# electronics_2_2023.net
KiCad netlist of a schematic drawn in EAGLE
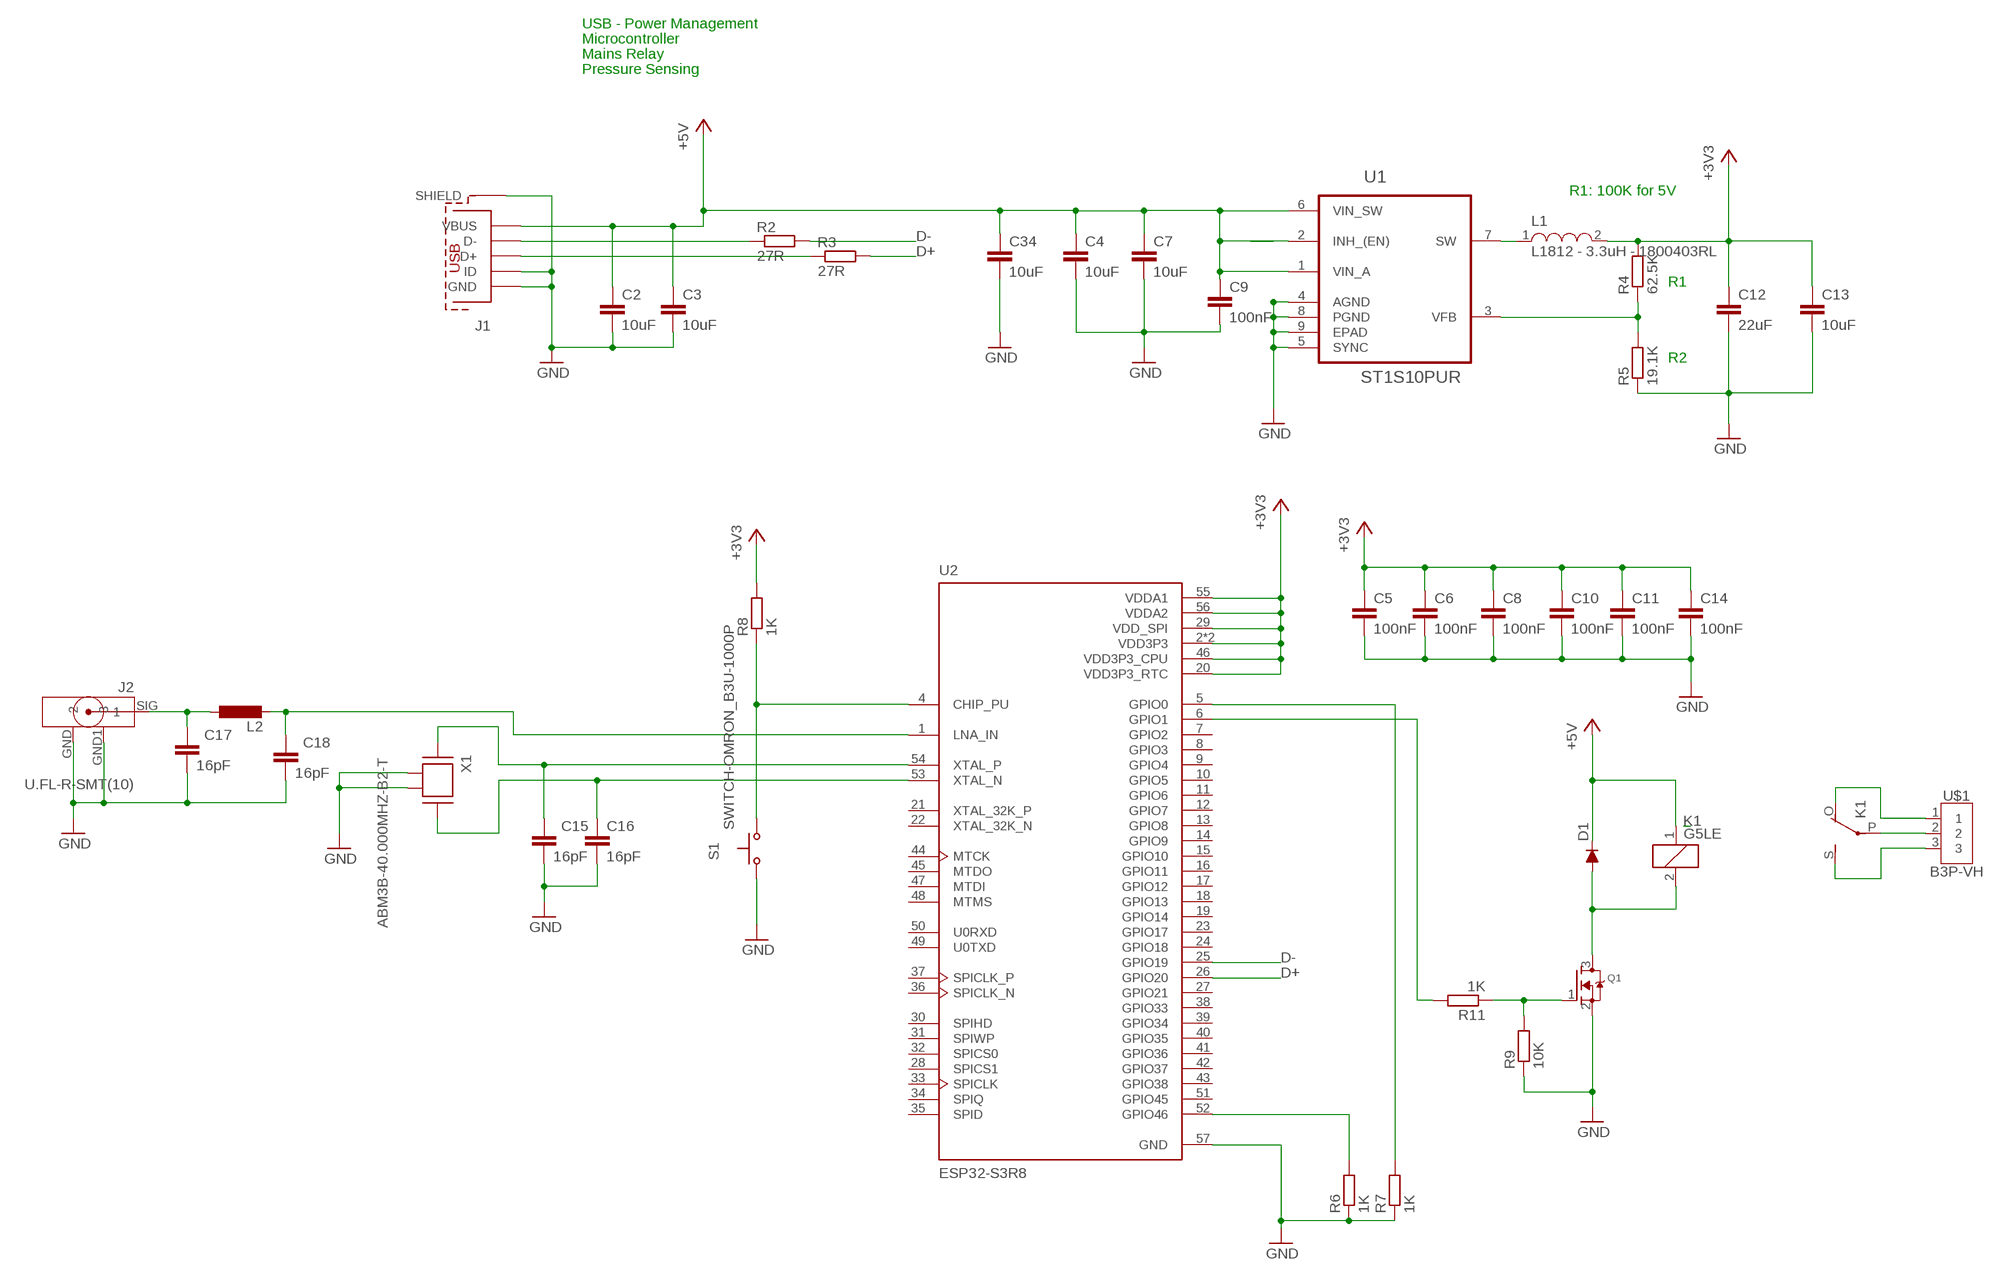
[diagram p0: schematic, sheet 1]
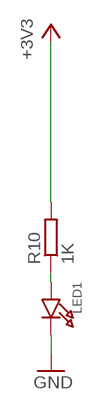
[diagram p1: schematic, sheet 2]

(export (version "E")
  (design (tool "Eeschema 10.0.6"))
  (components
    (comp (ref "C2")
      (value "10uF")
      (footprint "eagle-import:C0603")
      (libsource (lib "eagle-import") (part "C-EUC0603"))
    )
    (comp (ref "C3")
      (value "10uF")
      (footprint "eagle-import:C0603")
      (libsource (lib "eagle-import") (part "C-EUC0603"))
    )
    (comp (ref "C4")
      (value "10uF")
      (footprint "eagle-import:C0603")
      (libsource (lib "eagle-import") (part "resistor_C-EUC0603"))
    )
    (comp (ref "C5")
      (value "100nF")
      (footprint "eagle-import:C0402")
      (libsource (lib "eagle-import") (part "C-EUC0402"))
    )
    (comp (ref "C6")
      (value "100nF")
      (footprint "eagle-import:C0402")
      (libsource (lib "eagle-import") (part "C-EUC0402"))
    )
    (comp (ref "C7")
      (value "10uF")
      (footprint "eagle-import:C0603")
      (libsource (lib "eagle-import") (part "resistor_C-EUC0603"))
    )
    (comp (ref "C8")
      (value "100nF")
      (footprint "eagle-import:C0402")
      (libsource (lib "eagle-import") (part "C-EUC0402"))
    )
    (comp (ref "C9")
      (value "100nF")
      (footprint "eagle-import:C0402")
      (libsource (lib "eagle-import") (part "resistor_C-EUC0402"))
    )
    (comp (ref "C10")
      (value "100nF")
      (footprint "eagle-import:C0402")
      (libsource (lib "eagle-import") (part "C-EUC0402"))
    )
    (comp (ref "C11")
      (value "100nF")
      (footprint "eagle-import:C0402")
      (libsource (lib "eagle-import") (part "C-EUC0402"))
    )
    (comp (ref "C12")
      (value "22uF")
      (footprint "eagle-import:C0603")
      (libsource (lib "eagle-import") (part "resistor_C-EUC0603"))
    )
    (comp (ref "C13")
      (value "10uF")
      (footprint "eagle-import:C0603")
      (libsource (lib "eagle-import") (part "resistor_C-EUC0603"))
    )
    (comp (ref "C14")
      (value "100nF")
      (footprint "eagle-import:C0402")
      (libsource (lib "eagle-import") (part "C-EUC0402"))
    )
    (comp (ref "C15")
      (value "16pF")
      (footprint "eagle-import:C0402")
      (libsource (lib "eagle-import") (part "C-EUC0402"))
    )
    (comp (ref "C16")
      (value "16pF")
      (footprint "eagle-import:C0402")
      (libsource (lib "eagle-import") (part "C-EUC0402"))
    )
    (comp (ref "C17")
      (value "16pF")
      (footprint "eagle-import:C0402")
      (libsource (lib "eagle-import") (part "C-EUC0402"))
    )
    (comp (ref "C18")
      (value "16pF")
      (footprint "eagle-import:C0402")
      (libsource (lib "eagle-import") (part "C-EUC0402"))
    )
    (comp (ref "C34")
      (value "10uF")
      (footprint "eagle-import:C0603")
      (libsource (lib "eagle-import") (part "resistor_C-EUC0603"))
    )
    (comp (ref "D1")
      (value "DIODE_DIODE-SOD123")
      (footprint "eagle-import:DIODE_SOD123")
      (libsource (lib "eagle-import") (part "DIODE_DIODE-SOD123"))
    )
    (comp (ref "J1")
      (value "MICRO-USB-SOCKET")
      (footprint "eagle-import:629105136821")
      (libsource (lib "eagle-import") (part "MICRO-USB-SOCKET"))
    )
    (comp (ref "J2")
      (value "U.FL-R-SMT(10)")
      (footprint "eagle-import:U.FL-R-SMT(10)")
      (fields
        (field (name "DIGIKEY_PART_NUMBER") "H9161CT-ND")
        (field (name "MANUFACTURER") "Hirose Electric Co Ltd")
        (field (name "CREATED_BY") "PCBLayout.com")
      )
      (libsource (lib "eagle-import") (part "U.FL-R-SMT(10)"))
    )
    (comp (ref "K1")
      (value "G5LE")
      (footprint "eagle-import:G5LE")
      (libsource (lib "eagle-import") (part "G5LE"))
    )
    (comp (ref "L1")
      (value "L1812 - 3.3uH - 1800403RL")
      (footprint "eagle-import:L1812")
      (libsource (lib "eagle-import") (part "INDUCTOR-L1812"))
    )
    (comp (ref "L2")
      (value "L-EUL2012C")
      (footprint "eagle-import:L2012C")
      (libsource (lib "eagle-import") (part "L-EUL2012C"))
    )
    (comp (ref "Q1")
      (value "MOSFET-NREFLOW")
      (footprint "eagle-import:SOT23")
      (libsource (lib "eagle-import") (part "MOSFET-NREFLOW"))
    )
    (comp (ref "R2")
      (value "27R")
      (footprint "eagle-import:R0402")
      (libsource (lib "eagle-import") (part "resistor_348_R-EU_R0402"))
    )
    (comp (ref "R3")
      (value "27R")
      (footprint "eagle-import:R0402")
      (libsource (lib "eagle-import") (part "resistor_348_R-EU_R0402"))
    )
    (comp (ref "R4")
      (value "62.5K")
      (footprint "eagle-import:R0402")
      (libsource (lib "eagle-import") (part "R-EU_R0402"))
    )
    (comp (ref "R5")
      (value "19.1K")
      (footprint "eagle-import:R0402")
      (libsource (lib "eagle-import") (part "R-EU_R0402"))
    )
    (comp (ref "R6")
      (value "1K")
      (footprint "eagle-import:R0402")
      (libsource (lib "eagle-import") (part "resistor_348_R-EU_R0402"))
    )
    (comp (ref "R7")
      (value "1K")
      (footprint "eagle-import:R0402")
      (libsource (lib "eagle-import") (part "resistor_348_R-EU_R0402"))
    )
    (comp (ref "R8")
      (value "1K")
      (footprint "eagle-import:R0402")
      (libsource (lib "eagle-import") (part "resistor_348_R-EU_R0402"))
    )
    (comp (ref "R9")
      (value "10K")
      (footprint "eagle-import:R0402")
      (libsource (lib "eagle-import") (part "resistor_348_R-EU_R0402"))
    )
    (comp (ref "R11")
      (value "1K")
      (footprint "eagle-import:R0402")
      (libsource (lib "eagle-import") (part "resistor_348_R-EU_R0402"))
    )
    (comp (ref "S1")
      (value "SWITCH-OMRON_B3U-1000P")
      (footprint "eagle-import:SWITCH-OMRON_B3U-1000P")
      (libsource (lib "eagle-import") (part "SWITCH-OMRON_B3U-1000P"))
    )
    (comp (ref "U$1")
      (value "B3P-VH")
      (footprint "eagle-import:B3P-VH_396_3N")
      (fields (field (name "MANUFACTURER") " JST Sales America Inc."))
      (libsource (lib "eagle-import") (part "B3P-VH"))
    )
    (comp (ref "U1")
      (value "ST1S10PUR")
      (footprint "eagle-import:DFN400X400X100-9N")
      (libsource (lib "eagle-import") (part "ST1S10PUR"))
    )
    (comp (ref "U2")
      (value "ESP32-S3R8")
      (footprint "eagle-import:QFN40P700X700X90-57N")
      (fields (field (name "MF") "Espressif Systems"))
      (libsource (lib "eagle-import") (part "ESP32-S3R8"))
    )
    (comp (ref "X1")
      (value "ABM3B-40.000MHZ-B2-T")
      (footprint "eagle-import:ABM3B-40.000MHZ-B2-T")
      (fields
        (field (name "DIGIKEY_PART_NUMBER") "535-9132-2-ND")
        (field (name "MANUFACTURER") "Abracon LLC")
        (field (name "CREATED_BY") "PCBLayout.com")
      )
      (libsource (lib "eagle-import") (part "ABM3B-40.000MHZ-B2-T"))
    )
    (comp (ref "LED1")
      (value "LED0603")
      (footprint "eagle-import:CHIPLED_0603")
      (libsource (lib "eagle-import") (part "LED0603"))
    )
    (comp (ref "R10")
      (value "1K")
      (footprint "eagle-import:R0402")
      (libsource (lib "eagle-import") (part "R-EU_R0402"))
    )
  )
  (nets
    (net (code "1") (name "+3V3") (class "Default")
      (node (ref "C10") (pin "1") (pinfunction "1_1") (pintype "passive"))
      (node (ref "C11") (pin "1") (pinfunction "1_1") (pintype "passive"))
      (node (ref "C12") (pin "1") (pinfunction "1_1") (pintype "passive"))
      (node (ref "C13") (pin "1") (pinfunction "1_1") (pintype "passive"))
      (node (ref "C14") (pin "1") (pinfunction "1_1") (pintype "passive"))
      (node (ref "C5") (pin "1") (pinfunction "1_1") (pintype "passive"))
      (node (ref "C6") (pin "1") (pinfunction "1_1") (pintype "passive"))
      (node (ref "C8") (pin "1") (pinfunction "1_1") (pintype "passive"))
      (node (ref "L1") (pin "2") (pinfunction "2_2") (pintype "passive"))
      (node (ref "R10") (pin "2") (pinfunction "2_2") (pintype "passive"))
      (node (ref "R4") (pin "2") (pinfunction "2_2") (pintype "passive"))
      (node (ref "R8") (pin "2") (pinfunction "2_2") (pintype "passive"))
      (node (ref "U2") (pin "2") (pinfunction "VDD3P3_2") (pintype "power_in"))
      (node (ref "U2") (pin "20") (pinfunction "VDD3P3_RTC_20") (pintype "power_in"))
      (node (ref "U2") (pin "29") (pinfunction "VDD_SPI_29") (pintype "power_in"))
      (node (ref "U2") (pin "3") (pinfunction "VDD3P3_3") (pintype "power_in"))
      (node (ref "U2") (pin "46") (pinfunction "VDD3P3_CPU_46") (pintype "power_in"))
      (node (ref "U2") (pin "55") (pinfunction "VDDA1_55") (pintype "power_in"))
      (node (ref "U2") (pin "56") (pinfunction "VDDA2_56") (pintype "power_in"))
    )
    (net (code "2") (name "+5V") (class "Default")
      (node (ref "C2") (pin "1") (pinfunction "1_1") (pintype "passive"))
      (node (ref "C3") (pin "1") (pinfunction "1_1") (pintype "passive"))
      (node (ref "C34") (pin "1") (pinfunction "1_1") (pintype "passive"))
      (node (ref "C4") (pin "1") (pinfunction "1_1") (pintype "passive"))
      (node (ref "C7") (pin "1") (pinfunction "1_1") (pintype "passive"))
      (node (ref "C9") (pin "1") (pinfunction "1_1") (pintype "passive"))
      (node (ref "D1") (pin "C") (pinfunction "C_C") (pintype "passive"))
      (node (ref "J1") (pin "1") (pinfunction "VBUS_1") (pintype "passive"))
      (node (ref "K1") (pin "1") (pinfunction "1_1") (pintype "passive"))
      (node (ref "U1") (pin "1") (pinfunction "VIN_A_1") (pintype "input"))
      (node (ref "U1") (pin "2") (pinfunction "INH_(EN)_2") (pintype "passive"))
      (node (ref "U1") (pin "6") (pinfunction "VIN_SW_6") (pintype "passive"))
    )
    (net (code "3") (name "D+") (class "Default")
      (node (ref "R3") (pin "2") (pinfunction "2_2") (pintype "passive"))
      (node (ref "U2") (pin "26") (pinfunction "GPIO20_26") (pintype "bidirectional"))
    )
    (net (code "4") (name "D-") (class "Default")
      (node (ref "R2") (pin "2") (pinfunction "2_2") (pintype "passive"))
      (node (ref "U2") (pin "25") (pinfunction "GPIO19_25") (pintype "bidirectional"))
    )
    (net (code "5") (name "GND") (class "Default")
      (node (ref "C10") (pin "2") (pinfunction "2_2") (pintype "passive"))
      (node (ref "C11") (pin "2") (pinfunction "2_2") (pintype "passive"))
      (node (ref "C12") (pin "2") (pinfunction "2_2") (pintype "passive"))
      (node (ref "C13") (pin "2") (pinfunction "2_2") (pintype "passive"))
      (node (ref "C14") (pin "2") (pinfunction "2_2") (pintype "passive"))
      (node (ref "C15") (pin "2") (pinfunction "2_2") (pintype "passive"))
      (node (ref "C16") (pin "2") (pinfunction "2_2") (pintype "passive"))
      (node (ref "C17") (pin "2") (pinfunction "2_2") (pintype "passive"))
      (node (ref "C18") (pin "2") (pinfunction "2_2") (pintype "passive"))
      (node (ref "C2") (pin "2") (pinfunction "2_2") (pintype "passive"))
      (node (ref "C3") (pin "2") (pinfunction "2_2") (pintype "passive"))
      (node (ref "C34") (pin "2") (pinfunction "2_2") (pintype "passive"))
      (node (ref "C4") (pin "2") (pinfunction "2_2") (pintype "passive"))
      (node (ref "C5") (pin "2") (pinfunction "2_2") (pintype "passive"))
      (node (ref "C6") (pin "2") (pinfunction "2_2") (pintype "passive"))
      (node (ref "C7") (pin "2") (pinfunction "2_2") (pintype "passive"))
      (node (ref "C8") (pin "2") (pinfunction "2_2") (pintype "passive"))
      (node (ref "C9") (pin "2") (pinfunction "2_2") (pintype "passive"))
      (node (ref "J1") (pin "4") (pinfunction "ID_4") (pintype "passive"))
      (node (ref "J1") (pin "5") (pinfunction "GND_5") (pintype "passive"))
      (node (ref "J1") (pin "SHELL") (pinfunction "SHIELD_SHELL") (pintype "passive"))
      (node (ref "J1") (pin "SHELL1") (pinfunction "SHIELD_SHELL1") (pintype "passive"))
      (node (ref "J1") (pin "SHELL2") (pinfunction "SHIELD_SHELL2") (pintype "passive"))
      (node (ref "J1") (pin "SHELL3") (pinfunction "SHIELD_SHELL3") (pintype "passive"))
      (node (ref "J2") (pin "GND") (pinfunction "2_GND") (pintype "passive"))
      (node (ref "J2") (pin "GND1") (pinfunction "3_GND1") (pintype "passive"))
      (node (ref "LED1") (pin "C") (pinfunction "C_C") (pintype "passive"))
      (node (ref "Q1") (pin "2") (pinfunction "S_2") (pintype "bidirectional"))
      (node (ref "R5") (pin "1") (pinfunction "1_1") (pintype "passive"))
      (node (ref "R6") (pin "1") (pinfunction "1_1") (pintype "passive"))
      (node (ref "R7") (pin "1") (pinfunction "1_1") (pintype "passive"))
      (node (ref "R9") (pin "1") (pinfunction "1_1") (pintype "passive"))
      (node (ref "S1") (pin "1") (pinfunction "P_1") (pintype "passive"))
      (node (ref "U1") (pin "4") (pinfunction "AGND_4") (pintype "power_in"))
      (node (ref "U1") (pin "5") (pinfunction "SYNC_5") (pintype "passive"))
      (node (ref "U1") (pin "8") (pinfunction "PGND_8") (pintype "power_in"))
      (node (ref "U1") (pin "9") (pinfunction "EPAD_9") (pintype "passive"))
      (node (ref "U2") (pin "57") (pinfunction "GND_57") (pintype "power_in"))
      (node (ref "X1") (pin "2") (pinfunction "2_2") (pintype "passive"))
      (node (ref "X1") (pin "4") (pinfunction "4_4") (pintype "passive"))
    )
    (net (code "6") (name "Net-(J1-D+)") (class "Default")
      (node (ref "J1") (pin "3") (pinfunction "D+_3") (pintype "passive"))
      (node (ref "R3") (pin "1") (pinfunction "1_1") (pintype "passive"))
    )
    (net (code "7") (name "Net-(J1-D-)") (class "Default")
      (node (ref "J1") (pin "2") (pinfunction "D-_2") (pintype "passive"))
      (node (ref "R2") (pin "1") (pinfunction "1_1") (pintype "passive"))
    )
    (net (code "8") (name "Net-(J2-1)") (class "Default")
      (node (ref "C17") (pin "1") (pinfunction "1_1") (pintype "passive"))
      (node (ref "J2") (pin "SIG") (pinfunction "1_SIG") (pintype "passive"))
      (node (ref "L2") (pin "1") (pinfunction "1_1") (pintype "passive"))
    )
    (net (code "9") (name "Net-(K1-PadO)") (class "Default")
      (node (ref "K1") (pin "O") (pinfunction "O_O") (pintype "passive"))
      (node (ref "U$1") (pin "1") (pinfunction "1_1") (pintype "bidirectional"))
    )
    (net (code "10") (name "Net-(K1-PadP)") (class "Default")
      (node (ref "K1") (pin "P") (pinfunction "P_P") (pintype "passive"))
      (node (ref "U$1") (pin "2") (pinfunction "2_2") (pintype "bidirectional"))
    )
    (net (code "11") (name "Net-(K1-PadS)") (class "Default")
      (node (ref "K1") (pin "S") (pinfunction "S_S") (pintype "passive"))
      (node (ref "U$1") (pin "3") (pinfunction "3_3") (pintype "bidirectional"))
    )
    (net (code "12") (name "Net-(LED1-PadA)") (class "Default")
      (node (ref "LED1") (pin "A") (pinfunction "A_A") (pintype "passive"))
      (node (ref "R10") (pin "1") (pinfunction "1_1") (pintype "passive"))
    )
    (net (code "13") (name "Net-(Q1-D)") (class "Default")
      (node (ref "D1") (pin "A") (pinfunction "A_A") (pintype "passive"))
      (node (ref "K1") (pin "2") (pinfunction "2_2") (pintype "passive"))
      (node (ref "Q1") (pin "3") (pinfunction "D_3") (pintype "bidirectional"))
    )
    (net (code "14") (name "Net-(Q1-G)") (class "Default")
      (node (ref "Q1") (pin "1") (pinfunction "G_1") (pintype "bidirectional"))
      (node (ref "R11") (pin "1") (pinfunction "1_1") (pintype "passive"))
      (node (ref "R9") (pin "2") (pinfunction "2_2") (pintype "passive"))
    )
    (net (code "15") (name "Net-(S1-S)") (class "Default")
      (node (ref "R8") (pin "1") (pinfunction "1_1") (pintype "passive"))
      (node (ref "S1") (pin "2") (pinfunction "S_2") (pintype "passive"))
      (node (ref "U2") (pin "4") (pinfunction "CHIP_PU_4") (pintype "input"))
    )
    (net (code "16") (name "Net-(U1-SW)") (class "Default")
      (node (ref "L1") (pin "1") (pinfunction "1_1") (pintype "passive"))
      (node (ref "U1") (pin "7") (pinfunction "SW_7") (pintype "passive"))
    )
    (net (code "17") (name "Net-(U1-VFB)") (class "Default")
      (node (ref "R4") (pin "1") (pinfunction "1_1") (pintype "passive"))
      (node (ref "R5") (pin "2") (pinfunction "2_2") (pintype "passive"))
      (node (ref "U1") (pin "3") (pinfunction "VFB_3") (pintype "passive"))
    )
    (net (code "18") (name "Net-(U2-GPIO0)") (class "Default")
      (node (ref "R7") (pin "2") (pinfunction "2_2") (pintype "passive"))
      (node (ref "U2") (pin "5") (pinfunction "GPIO0_5") (pintype "bidirectional"))
    )
    (net (code "19") (name "Net-(U2-GPIO1)") (class "Default")
      (node (ref "R11") (pin "2") (pinfunction "2_2") (pintype "passive"))
      (node (ref "U2") (pin "6") (pinfunction "GPIO1_6") (pintype "bidirectional"))
    )
    (net (code "20") (name "Net-(U2-GPIO46)") (class "Default")
      (node (ref "R6") (pin "2") (pinfunction "2_2") (pintype "passive"))
      (node (ref "U2") (pin "52") (pinfunction "GPIO46_52") (pintype "bidirectional"))
    )
    (net (code "21") (name "Net-(U2-LNA_IN)") (class "Default")
      (node (ref "C18") (pin "1") (pinfunction "1_1") (pintype "passive"))
      (node (ref "L2") (pin "2") (pinfunction "2_2") (pintype "passive"))
      (node (ref "U2") (pin "1") (pinfunction "LNA_IN_1") (pintype "bidirectional"))
    )
    (net (code "22") (name "Net-(U2-XTAL_N)") (class "Default")
      (node (ref "C16") (pin "1") (pinfunction "1_1") (pintype "passive"))
      (node (ref "U2") (pin "53") (pinfunction "XTAL_N_53") (pintype "output"))
      (node (ref "X1") (pin "3") (pinfunction "3_3") (pintype "passive"))
    )
    (net (code "23") (name "Net-(U2-XTAL_P)") (class "Default")
      (node (ref "C15") (pin "1") (pinfunction "1_1") (pintype "passive"))
      (node (ref "U2") (pin "54") (pinfunction "XTAL_P_54") (pintype "input"))
      (node (ref "X1") (pin "1") (pinfunction "1_1") (pintype "passive"))
    )
    (net (code "24") (name "unconnected-(U2-GPIO2-Pad7)") (class "Default")
      (node (ref "U2") (pin "7") (pinfunction "GPIO2_7") (pintype "bidirectional"))
    )
    (net (code "25") (name "unconnected-(U2-GPIO3-Pad8)") (class "Default")
      (node (ref "U2") (pin "8") (pinfunction "GPIO3_8") (pintype "bidirectional"))
    )
    (net (code "26") (name "unconnected-(U2-GPIO4-Pad9)") (class "Default")
      (node (ref "U2") (pin "9") (pinfunction "GPIO4_9") (pintype "bidirectional"))
    )
    (net (code "27") (name "unconnected-(U2-GPIO5-Pad10)") (class "Default")
      (node (ref "U2") (pin "10") (pinfunction "GPIO5_10") (pintype "bidirectional"))
    )
    (net (code "28") (name "unconnected-(U2-GPIO6-Pad11)") (class "Default")
      (node (ref "U2") (pin "11") (pinfunction "GPIO6_11") (pintype "bidirectional"))
    )
    (net (code "29") (name "unconnected-(U2-GPIO7-Pad12)") (class "Default")
      (node (ref "U2") (pin "12") (pinfunction "GPIO7_12") (pintype "bidirectional"))
    )
    (net (code "30") (name "unconnected-(U2-GPIO8-Pad13)") (class "Default")
      (node (ref "U2") (pin "13") (pinfunction "GPIO8_13") (pintype "bidirectional"))
    )
    (net (code "31") (name "unconnected-(U2-GPIO9-Pad14)") (class "Default")
      (node (ref "U2") (pin "14") (pinfunction "GPIO9_14") (pintype "bidirectional"))
    )
    (net (code "32") (name "unconnected-(U2-GPIO10-Pad15)") (class "Default")
      (node (ref "U2") (pin "15") (pinfunction "GPIO10_15") (pintype "bidirectional"))
    )
    (net (code "33") (name "unconnected-(U2-GPIO11-Pad16)") (class "Default")
      (node (ref "U2") (pin "16") (pinfunction "GPIO11_16") (pintype "bidirectional"))
    )
    (net (code "34") (name "unconnected-(U2-GPIO12-Pad17)") (class "Default")
      (node (ref "U2") (pin "17") (pinfunction "GPIO12_17") (pintype "bidirectional"))
    )
    (net (code "35") (name "unconnected-(U2-GPIO13-Pad18)") (class "Default")
      (node (ref "U2") (pin "18") (pinfunction "GPIO13_18") (pintype "bidirectional"))
    )
    (net (code "36") (name "unconnected-(U2-GPIO14-Pad19)") (class "Default")
      (node (ref "U2") (pin "19") (pinfunction "GPIO14_19") (pintype "bidirectional"))
    )
    (net (code "37") (name "unconnected-(U2-GPIO17-Pad23)") (class "Default")
      (node (ref "U2") (pin "23") (pinfunction "GPIO17_23") (pintype "bidirectional"))
    )
    (net (code "38") (name "unconnected-(U2-GPIO18-Pad24)") (class "Default")
      (node (ref "U2") (pin "24") (pinfunction "GPIO18_24") (pintype "bidirectional"))
    )
    (net (code "39") (name "unconnected-(U2-GPIO21-Pad27)") (class "Default")
      (node (ref "U2") (pin "27") (pinfunction "GPIO21_27") (pintype "bidirectional"))
    )
    (net (code "40") (name "unconnected-(U2-GPIO33-Pad38)") (class "Default")
      (node (ref "U2") (pin "38") (pinfunction "GPIO33_38") (pintype "bidirectional"))
    )
    (net (code "41") (name "unconnected-(U2-GPIO34-Pad39)") (class "Default")
      (node (ref "U2") (pin "39") (pinfunction "GPIO34_39") (pintype "bidirectional"))
    )
    (net (code "42") (name "unconnected-(U2-GPIO35-Pad40)") (class "Default")
      (node (ref "U2") (pin "40") (pinfunction "GPIO35_40") (pintype "bidirectional"))
    )
    (net (code "43") (name "unconnected-(U2-GPIO36-Pad41)") (class "Default")
      (node (ref "U2") (pin "41") (pinfunction "GPIO36_41") (pintype "bidirectional"))
    )
    (net (code "44") (name "unconnected-(U2-GPIO37-Pad42)") (class "Default")
      (node (ref "U2") (pin "42") (pinfunction "GPIO37_42") (pintype "bidirectional"))
    )
    (net (code "45") (name "unconnected-(U2-GPIO38-Pad43)") (class "Default")
      (node (ref "U2") (pin "43") (pinfunction "GPIO38_43") (pintype "bidirectional"))
    )
    (net (code "46") (name "unconnected-(U2-GPIO45-Pad51)") (class "Default")
      (node (ref "U2") (pin "51") (pinfunction "GPIO45_51") (pintype "bidirectional"))
    )
    (net (code "47") (name "unconnected-(U2-MTCK-Pad44)") (class "Default")
      (node (ref "U2") (pin "44") (pinfunction "MTCK_44") (pintype "bidirectional"))
    )
    (net (code "48") (name "unconnected-(U2-MTDI-Pad47)") (class "Default")
      (node (ref "U2") (pin "47") (pinfunction "MTDI_47") (pintype "bidirectional"))
    )
    (net (code "49") (name "unconnected-(U2-MTDO-Pad45)") (class "Default")
      (node (ref "U2") (pin "45") (pinfunction "MTDO_45") (pintype "bidirectional"))
    )
    (net (code "50") (name "unconnected-(U2-MTMS-Pad48)") (class "Default")
      (node (ref "U2") (pin "48") (pinfunction "MTMS_48") (pintype "bidirectional"))
    )
    (net (code "51") (name "unconnected-(U2-SPICLK-Pad33)") (class "Default")
      (node (ref "U2") (pin "33") (pinfunction "SPICLK_33") (pintype "bidirectional"))
    )
    (net (code "52") (name "unconnected-(U2-SPICLK_N-Pad36)") (class "Default")
      (node (ref "U2") (pin "36") (pinfunction "SPICLK_N_36") (pintype "bidirectional"))
    )
    (net (code "53") (name "unconnected-(U2-SPICLK_P-Pad37)") (class "Default")
      (node (ref "U2") (pin "37") (pinfunction "SPICLK_P_37") (pintype "bidirectional"))
    )
    (net (code "54") (name "unconnected-(U2-SPICS0-Pad32)") (class "Default")
      (node (ref "U2") (pin "32") (pinfunction "SPICS0_32") (pintype "bidirectional"))
    )
    (net (code "55") (name "unconnected-(U2-SPICS1-Pad28)") (class "Default")
      (node (ref "U2") (pin "28") (pinfunction "SPICS1_28") (pintype "bidirectional"))
    )
    (net (code "56") (name "unconnected-(U2-SPID-Pad35)") (class "Default")
      (node (ref "U2") (pin "35") (pinfunction "SPID_35") (pintype "bidirectional"))
    )
    (net (code "57") (name "unconnected-(U2-SPIHD-Pad30)") (class "Default")
      (node (ref "U2") (pin "30") (pinfunction "SPIHD_30") (pintype "bidirectional"))
    )
    (net (code "58") (name "unconnected-(U2-SPIQ-Pad34)") (class "Default")
      (node (ref "U2") (pin "34") (pinfunction "SPIQ_34") (pintype "bidirectional"))
    )
    (net (code "59") (name "unconnected-(U2-SPIWP-Pad31)") (class "Default")
      (node (ref "U2") (pin "31") (pinfunction "SPIWP_31") (pintype "bidirectional"))
    )
    (net (code "60") (name "unconnected-(U2-U0RXD-Pad50)") (class "Default")
      (node (ref "U2") (pin "50") (pinfunction "U0RXD_50") (pintype "bidirectional"))
    )
    (net (code "61") (name "unconnected-(U2-U0TXD-Pad49)") (class "Default")
      (node (ref "U2") (pin "49") (pinfunction "U0TXD_49") (pintype "bidirectional"))
    )
    (net (code "62") (name "unconnected-(U2-XTAL_32K_N-Pad22)") (class "Default")
      (node (ref "U2") (pin "22") (pinfunction "XTAL_32K_N_22") (pintype "bidirectional"))
    )
    (net (code "63") (name "unconnected-(U2-XTAL_32K_P-Pad21)") (class "Default")
      (node (ref "U2") (pin "21") (pinfunction "XTAL_32K_P_21") (pintype "bidirectional"))
    )
  )
)
